# untitled2.net
KiCad netlist of a schematic drawn in EAGLE
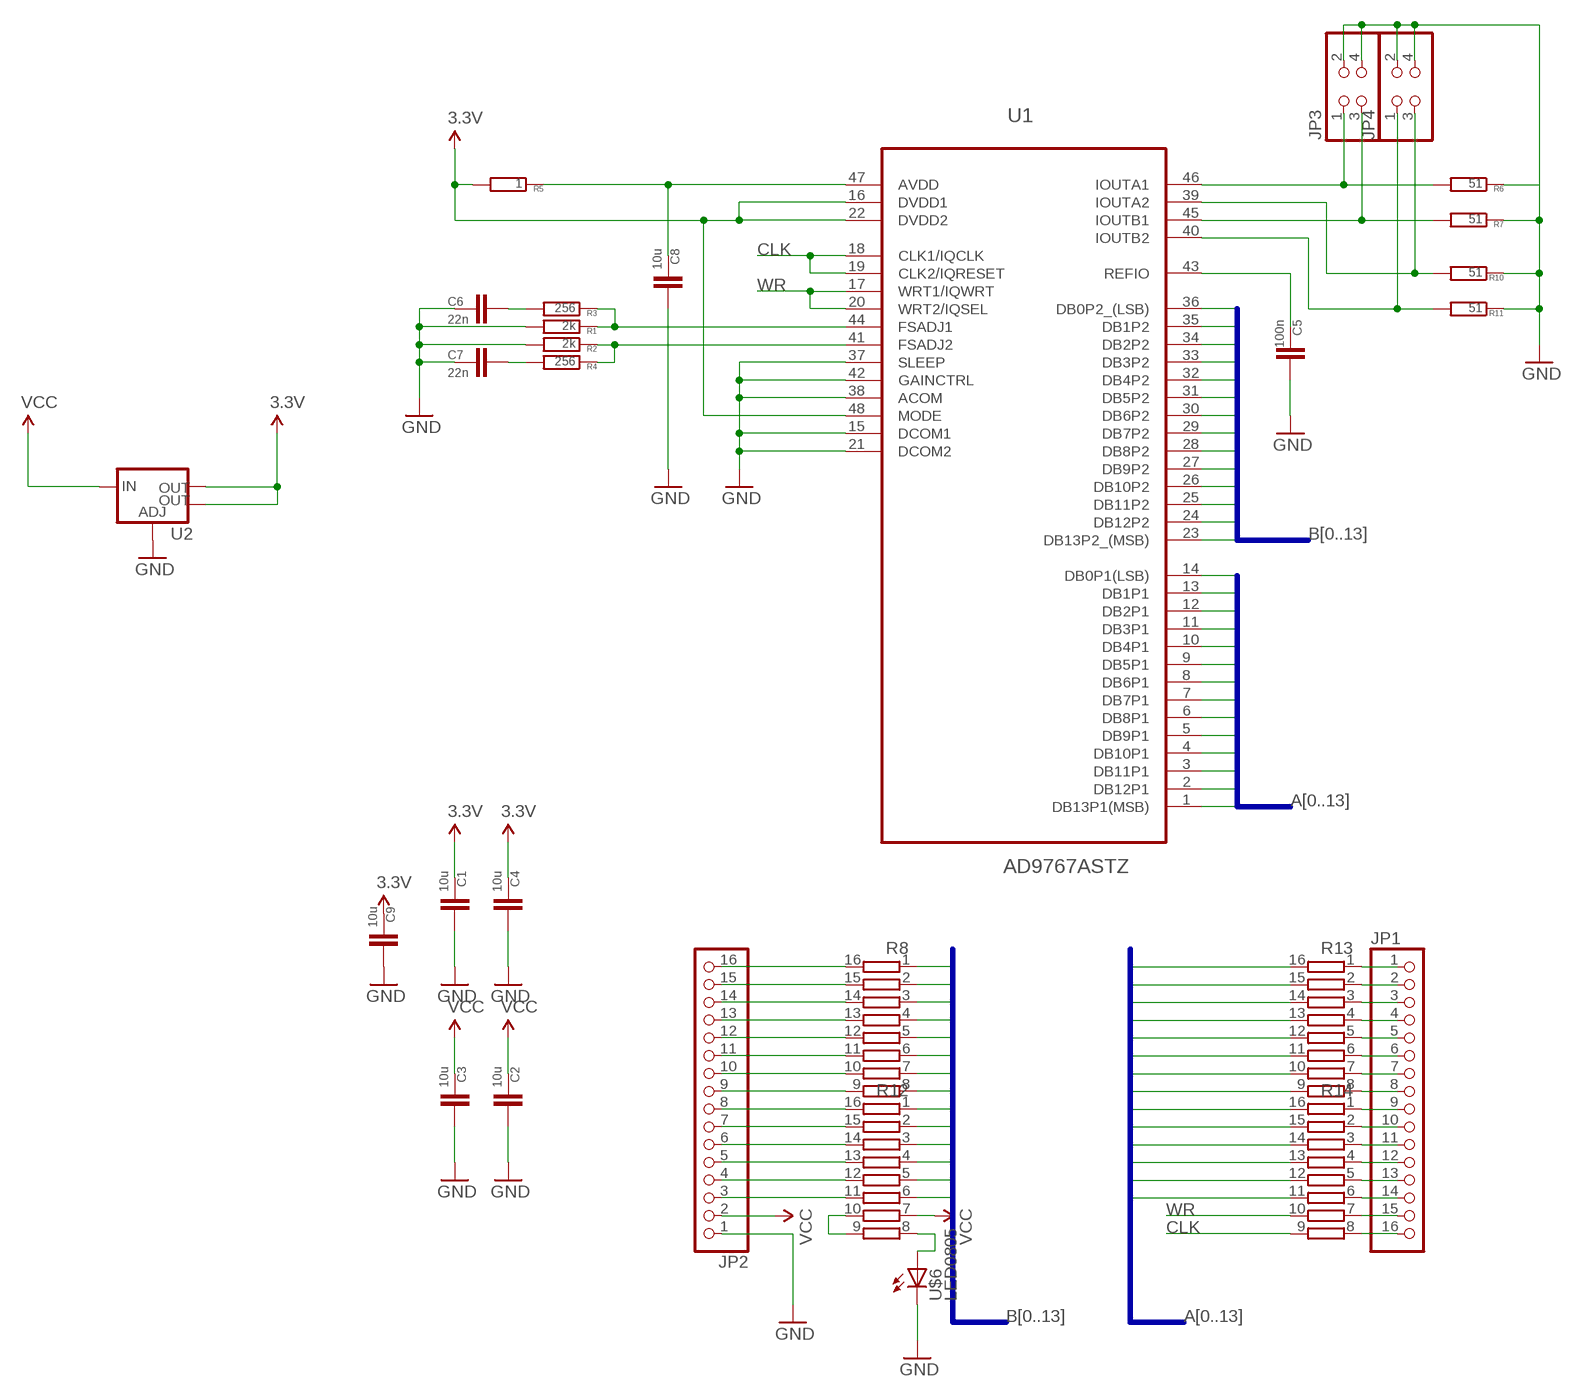
[diagram p0: schematic, sheet 1]

(export (version "E")
  (design (tool "Eeschema 10.0.6"))
  (components
    (comp (ref "C1")
      (value "10u")
      (footprint "eagle-import:C0805")
      (libsource (lib "eagle-import") (part "CC0805"))
    )
    (comp (ref "C2")
      (value "10u")
      (footprint "eagle-import:C0805")
      (libsource (lib "eagle-import") (part "CC0805"))
    )
    (comp (ref "C3")
      (value "10u")
      (footprint "eagle-import:C0805")
      (libsource (lib "eagle-import") (part "CC0805"))
    )
    (comp (ref "C4")
      (value "10u")
      (footprint "eagle-import:C0805")
      (libsource (lib "eagle-import") (part "CC0805"))
    )
    (comp (ref "C5")
      (value "100n")
      (footprint "eagle-import:C0805")
      (libsource (lib "eagle-import") (part "CC0805"))
    )
    (comp (ref "C6")
      (value "22n")
      (footprint "eagle-import:C0805")
      (libsource (lib "eagle-import") (part "CC0805"))
    )
    (comp (ref "C7")
      (value "22n")
      (footprint "eagle-import:C0805")
      (libsource (lib "eagle-import") (part "CC0805"))
    )
    (comp (ref "C8")
      (value "10u")
      (footprint "eagle-import:C0805")
      (libsource (lib "eagle-import") (part "CC0805"))
    )
    (comp (ref "C9")
      (value "10u")
      (footprint "eagle-import:C0805")
      (libsource (lib "eagle-import") (part "CC0805"))
    )
    (comp (ref "JP1")
      (value "PINHD-1X16_2.54")
      (footprint "eagle-import:1X16")
      (libsource (lib "eagle-import") (part "PINHD-1X16_2.54"))
    )
    (comp (ref "JP2")
      (value "PINHD-1X16_2.54")
      (footprint "eagle-import:1X16")
      (libsource (lib "eagle-import") (part "PINHD-1X16_2.54"))
    )
    (comp (ref "JP3")
      (value "PINHD-2X02_2.54-SMD")
      (footprint "eagle-import:2X02SMD")
      (libsource (lib "eagle-import") (part "PINHD-2X02_2.54-SMD"))
    )
    (comp (ref "JP4")
      (value "PINHD-2X02_2.54-SMD")
      (footprint "eagle-import:2X02SMD")
      (libsource (lib "eagle-import") (part "PINHD-2X02_2.54-SMD"))
    )
    (comp (ref "R1")
      (value "2k")
      (footprint "eagle-import:R0805")
      (libsource (lib "eagle-import") (part "R0805"))
    )
    (comp (ref "R2")
      (value "2k")
      (footprint "eagle-import:R0805")
      (libsource (lib "eagle-import") (part "R0805"))
    )
    (comp (ref "R3")
      (value "256")
      (footprint "eagle-import:R0805")
      (libsource (lib "eagle-import") (part "R0805"))
    )
    (comp (ref "R4")
      (value "256")
      (footprint "eagle-import:R0805")
      (libsource (lib "eagle-import") (part "R0805"))
    )
    (comp (ref "R5")
      (value "1")
      (footprint "eagle-import:0603")
      (libsource (lib "eagle-import") (part "R0603"))
    )
    (comp (ref "R6")
      (value "51")
      (footprint "eagle-import:R0805")
      (libsource (lib "eagle-import") (part "R0805"))
    )
    (comp (ref "R7")
      (value "51")
      (footprint "eagle-import:R0805")
      (libsource (lib "eagle-import") (part "R0805"))
    )
    (comp (ref "R8")
      (value "4816P-T01")
      (footprint "eagle-import:4816P")
      (fields (field (name "MF") "BOURNS, INC.") (field (name "MPN") "4816P-T01-684LF"))
      (libsource (lib "eagle-import") (part "4816P-T01"))
    )
    (comp (ref "R10")
      (value "51")
      (footprint "eagle-import:R0805")
      (libsource (lib "eagle-import") (part "R0805"))
    )
    (comp (ref "R11")
      (value "51")
      (footprint "eagle-import:R0805")
      (libsource (lib "eagle-import") (part "R0805"))
    )
    (comp (ref "R12")
      (value "4816P-T01")
      (footprint "eagle-import:4816P")
      (fields (field (name "MF") "BOURNS, INC.") (field (name "MPN") "4816P-T01-684LF"))
      (libsource (lib "eagle-import") (part "4816P-T01"))
    )
    (comp (ref "R13")
      (value "4816P-T01")
      (footprint "eagle-import:4816P")
      (fields (field (name "MF") "BOURNS, INC.") (field (name "MPN") "4816P-T01-684LF"))
      (libsource (lib "eagle-import") (part "4816P-T01"))
    )
    (comp (ref "R14")
      (value "4816P-T01")
      (footprint "eagle-import:4816P")
      (fields (field (name "MF") "BOURNS, INC.") (field (name "MPN") "4816P-T01-684LF"))
      (libsource (lib "eagle-import") (part "4816P-T01"))
    )
    (comp (ref "U$6")
      (value "LED0805")
      (footprint "eagle-import:0805-LED")
      (libsource (lib "eagle-import") (part "LED0805"))
    )
    (comp (ref "U1")
      (value "AD9767ASTZ")
      (footprint "eagle-import:QFP50P900X900X160-48N")
      (libsource (lib "eagle-import") (part "AD9767ASTZ"))
    )
    (comp (ref "U2")
      (value "V_REG_LM1117SOT223")
      (footprint "eagle-import:SOT223")
      (libsource (lib "eagle-import") (part "V_REG_LM1117SOT223"))
    )
  )
  (nets
    (net (code "1") (name "/A0") (class "Default")
      (node (ref "R14") (pin "11") (pinfunction "11_11") (pintype "passive"))
      (node (ref "U1") (pin "14") (pinfunction "DB0P1(LSB)_14") (pintype "bidirectional"))
    )
    (net (code "2") (name "/A1") (class "Default")
      (node (ref "R14") (pin "12") (pinfunction "12_12") (pintype "passive"))
      (node (ref "U1") (pin "13") (pinfunction "DB1P1_13") (pintype "bidirectional"))
    )
    (net (code "3") (name "/A2") (class "Default")
      (node (ref "R14") (pin "13") (pinfunction "13_13") (pintype "passive"))
      (node (ref "U1") (pin "12") (pinfunction "DB2P1_12") (pintype "bidirectional"))
    )
    (net (code "4") (name "/A3") (class "Default")
      (node (ref "R14") (pin "14") (pinfunction "14_14") (pintype "passive"))
      (node (ref "U1") (pin "11") (pinfunction "DB3P1_11") (pintype "bidirectional"))
    )
    (net (code "5") (name "/A4") (class "Default")
      (node (ref "R14") (pin "15") (pinfunction "15_15") (pintype "passive"))
      (node (ref "U1") (pin "10") (pinfunction "DB4P1_10") (pintype "bidirectional"))
    )
    (net (code "6") (name "/A5") (class "Default")
      (node (ref "R14") (pin "16") (pinfunction "16_16") (pintype "passive"))
      (node (ref "U1") (pin "9") (pinfunction "DB5P1_9") (pintype "bidirectional"))
    )
    (net (code "7") (name "/A6") (class "Default")
      (node (ref "R13") (pin "9") (pinfunction "9_9") (pintype "passive"))
      (node (ref "U1") (pin "8") (pinfunction "DB6P1_8") (pintype "bidirectional"))
    )
    (net (code "8") (name "/A7") (class "Default")
      (node (ref "R13") (pin "10") (pinfunction "10_10") (pintype "passive"))
      (node (ref "U1") (pin "7") (pinfunction "DB7P1_7") (pintype "bidirectional"))
    )
    (net (code "9") (name "/A8") (class "Default")
      (node (ref "R13") (pin "11") (pinfunction "11_11") (pintype "passive"))
      (node (ref "U1") (pin "6") (pinfunction "DB8P1_6") (pintype "bidirectional"))
    )
    (net (code "10") (name "/A9") (class "Default")
      (node (ref "R13") (pin "12") (pinfunction "12_12") (pintype "passive"))
      (node (ref "U1") (pin "5") (pinfunction "DB9P1_5") (pintype "bidirectional"))
    )
    (net (code "11") (name "/A10") (class "Default")
      (node (ref "R13") (pin "13") (pinfunction "13_13") (pintype "passive"))
      (node (ref "U1") (pin "4") (pinfunction "DB10P1_4") (pintype "bidirectional"))
    )
    (net (code "12") (name "/A11") (class "Default")
      (node (ref "R13") (pin "14") (pinfunction "14_14") (pintype "passive"))
      (node (ref "U1") (pin "3") (pinfunction "DB11P1_3") (pintype "bidirectional"))
    )
    (net (code "13") (name "/A12") (class "Default")
      (node (ref "R13") (pin "15") (pinfunction "15_15") (pintype "passive"))
      (node (ref "U1") (pin "2") (pinfunction "DB12P1_2") (pintype "bidirectional"))
    )
    (net (code "14") (name "/A13") (class "Default")
      (node (ref "R13") (pin "16") (pinfunction "16_16") (pintype "passive"))
      (node (ref "U1") (pin "1") (pinfunction "DB13P1(MSB)_1") (pintype "bidirectional"))
    )
    (net (code "16") (name "/B0") (class "Default")
      (node (ref "R8") (pin "1") (pinfunction "1_1") (pintype "passive"))
      (node (ref "U1") (pin "36") (pinfunction "DB0P2_(LSB)_36") (pintype "bidirectional"))
    )
    (net (code "17") (name "/B1") (class "Default")
      (node (ref "R8") (pin "2") (pinfunction "2_2") (pintype "passive"))
      (node (ref "U1") (pin "35") (pinfunction "DB1P2_35") (pintype "bidirectional"))
    )
    (net (code "18") (name "/B2") (class "Default")
      (node (ref "R8") (pin "3") (pinfunction "3_3") (pintype "passive"))
      (node (ref "U1") (pin "34") (pinfunction "DB2P2_34") (pintype "bidirectional"))
    )
    (net (code "19") (name "/B3") (class "Default")
      (node (ref "R8") (pin "4") (pinfunction "4_4") (pintype "passive"))
      (node (ref "U1") (pin "33") (pinfunction "DB3P2_33") (pintype "bidirectional"))
    )
    (net (code "20") (name "/B4") (class "Default")
      (node (ref "R8") (pin "5") (pinfunction "5_5") (pintype "passive"))
      (node (ref "U1") (pin "32") (pinfunction "DB4P2_32") (pintype "bidirectional"))
    )
    (net (code "21") (name "/B5") (class "Default")
      (node (ref "R8") (pin "6") (pinfunction "6_6") (pintype "passive"))
      (node (ref "U1") (pin "31") (pinfunction "DB5P2_31") (pintype "bidirectional"))
    )
    (net (code "22") (name "/B6") (class "Default")
      (node (ref "R8") (pin "7") (pinfunction "7_7") (pintype "passive"))
      (node (ref "U1") (pin "30") (pinfunction "DB6P2_30") (pintype "bidirectional"))
    )
    (net (code "23") (name "/B7") (class "Default")
      (node (ref "R8") (pin "8") (pinfunction "8_8") (pintype "passive"))
      (node (ref "U1") (pin "29") (pinfunction "DB7P2_29") (pintype "bidirectional"))
    )
    (net (code "24") (name "/B8") (class "Default")
      (node (ref "R12") (pin "1") (pinfunction "1_1") (pintype "passive"))
      (node (ref "U1") (pin "28") (pinfunction "DB8P2_28") (pintype "bidirectional"))
    )
    (net (code "25") (name "/B9") (class "Default")
      (node (ref "R12") (pin "2") (pinfunction "2_2") (pintype "passive"))
      (node (ref "U1") (pin "27") (pinfunction "DB9P2_27") (pintype "bidirectional"))
    )
    (net (code "26") (name "/B10") (class "Default")
      (node (ref "R12") (pin "3") (pinfunction "3_3") (pintype "passive"))
      (node (ref "U1") (pin "26") (pinfunction "DB10P2_26") (pintype "bidirectional"))
    )
    (net (code "27") (name "/B11") (class "Default")
      (node (ref "R12") (pin "4") (pinfunction "4_4") (pintype "passive"))
      (node (ref "U1") (pin "25") (pinfunction "DB11P2_25") (pintype "bidirectional"))
    )
    (net (code "28") (name "/B12") (class "Default")
      (node (ref "R12") (pin "5") (pinfunction "5_5") (pintype "passive"))
      (node (ref "U1") (pin "24") (pinfunction "DB12P2_24") (pintype "bidirectional"))
    )
    (net (code "29") (name "/B13") (class "Default")
      (node (ref "R12") (pin "6") (pinfunction "6_6") (pintype "passive"))
      (node (ref "U1") (pin "23") (pinfunction "DB13P2_(MSB)_23") (pintype "bidirectional"))
    )
    (net (code "31") (name "/CLK") (class "Default")
      (node (ref "R14") (pin "9") (pinfunction "9_9") (pintype "passive"))
      (node (ref "U1") (pin "18") (pinfunction "CLK1/IQCLK_18") (pintype "input"))
      (node (ref "U1") (pin "19") (pinfunction "CLK2/IQRESET_19") (pintype "input"))
    )
    (net (code "32") (name "/WR") (class "Default")
      (node (ref "R14") (pin "10") (pinfunction "10_10") (pintype "passive"))
      (node (ref "U1") (pin "17") (pinfunction "WRT1/IQWRT_17") (pintype "input"))
      (node (ref "U1") (pin "20") (pinfunction "WRT2/IQSEL_20") (pintype "input"))
    )
    (net (code "33") (name "3.3V") (class "Default")
      (node (ref "C1") (pin "2") (pinfunction "2_2") (pintype "passive"))
      (node (ref "C4") (pin "2") (pinfunction "2_2") (pintype "passive"))
      (node (ref "C9") (pin "2") (pinfunction "2_2") (pintype "passive"))
      (node (ref "R5") (pin "2") (pinfunction "2_2") (pintype "passive"))
      (node (ref "U1") (pin "16") (pinfunction "DVDD1_16") (pintype "power_in"))
      (node (ref "U1") (pin "22") (pinfunction "DVDD2_22") (pintype "power_in"))
      (node (ref "U1") (pin "48") (pinfunction "MODE_48") (pintype "passive"))
      (node (ref "U2") (pin "2") (pinfunction "OUT_2") (pintype "output"))
      (node (ref "U2") (pin "4") (pinfunction "OUT_4") (pintype "output"))
    )
    (net (code "34") (name "GND") (class "Default")
      (node (ref "C1") (pin "1") (pinfunction "1_1") (pintype "passive"))
      (node (ref "C2") (pin "1") (pinfunction "1_1") (pintype "passive"))
      (node (ref "C3") (pin "1") (pinfunction "1_1") (pintype "passive"))
      (node (ref "C4") (pin "1") (pinfunction "1_1") (pintype "passive"))
      (node (ref "C5") (pin "1") (pinfunction "1_1") (pintype "passive"))
      (node (ref "C6") (pin "2") (pinfunction "2_2") (pintype "passive"))
      (node (ref "C7") (pin "2") (pinfunction "2_2") (pintype "passive"))
      (node (ref "C8") (pin "1") (pinfunction "1_1") (pintype "passive"))
      (node (ref "C9") (pin "1") (pinfunction "1_1") (pintype "passive"))
      (node (ref "JP2") (pin "1") (pinfunction "1_1") (pintype "passive"))
      (node (ref "JP3") (pin "2") (pinfunction "2_2") (pintype "passive"))
      (node (ref "JP3") (pin "4") (pinfunction "4_4") (pintype "passive"))
      (node (ref "JP4") (pin "2") (pinfunction "2_2") (pintype "passive"))
      (node (ref "JP4") (pin "4") (pinfunction "4_4") (pintype "passive"))
      (node (ref "R1") (pin "2") (pinfunction "2_2") (pintype "passive"))
      (node (ref "R10") (pin "1") (pinfunction "1_1") (pintype "passive"))
      (node (ref "R11") (pin "1") (pinfunction "1_1") (pintype "passive"))
      (node (ref "R2") (pin "2") (pinfunction "2_2") (pintype "passive"))
      (node (ref "R6") (pin "1") (pinfunction "1_1") (pintype "passive"))
      (node (ref "R7") (pin "1") (pinfunction "1_1") (pintype "passive"))
      (node (ref "U$6") (pin "C") (pinfunction "C_C") (pintype "passive"))
      (node (ref "U1") (pin "15") (pinfunction "DCOM1_15") (pintype "passive"))
      (node (ref "U1") (pin "21") (pinfunction "DCOM2_21") (pintype "passive"))
      (node (ref "U1") (pin "37") (pinfunction "SLEEP_37") (pintype "passive"))
      (node (ref "U1") (pin "38") (pinfunction "ACOM_38") (pintype "passive"))
      (node (ref "U1") (pin "42") (pinfunction "GAINCTRL_42") (pintype "passive"))
      (node (ref "U2") (pin "1") (pinfunction "ADJ_1") (pintype "input"))
    )
    (net (code "35") (name "Net-(C6-Pad1)") (class "Default")
      (node (ref "C6") (pin "1") (pinfunction "1_1") (pintype "passive"))
      (node (ref "R3") (pin "2") (pinfunction "2_2") (pintype "passive"))
    )
    (net (code "36") (name "Net-(C7-Pad1)") (class "Default")
      (node (ref "C7") (pin "1") (pinfunction "1_1") (pintype "passive"))
      (node (ref "R4") (pin "2") (pinfunction "2_2") (pintype "passive"))
    )
    (net (code "37") (name "Net-(JP1-Pad1)") (class "Default")
      (node (ref "JP1") (pin "1") (pinfunction "1_1") (pintype "passive"))
      (node (ref "R13") (pin "1") (pinfunction "1_1") (pintype "passive"))
    )
    (net (code "38") (name "Net-(JP1-Pad2)") (class "Default")
      (node (ref "JP1") (pin "2") (pinfunction "2_2") (pintype "passive"))
      (node (ref "R13") (pin "2") (pinfunction "2_2") (pintype "passive"))
    )
    (net (code "39") (name "Net-(JP1-Pad3)") (class "Default")
      (node (ref "JP1") (pin "3") (pinfunction "3_3") (pintype "passive"))
      (node (ref "R13") (pin "3") (pinfunction "3_3") (pintype "passive"))
    )
    (net (code "40") (name "Net-(JP1-Pad4)") (class "Default")
      (node (ref "JP1") (pin "4") (pinfunction "4_4") (pintype "passive"))
      (node (ref "R13") (pin "4") (pinfunction "4_4") (pintype "passive"))
    )
    (net (code "41") (name "Net-(JP1-Pad5)") (class "Default")
      (node (ref "JP1") (pin "5") (pinfunction "5_5") (pintype "passive"))
      (node (ref "R13") (pin "5") (pinfunction "5_5") (pintype "passive"))
    )
    (net (code "42") (name "Net-(JP1-Pad6)") (class "Default")
      (node (ref "JP1") (pin "6") (pinfunction "6_6") (pintype "passive"))
      (node (ref "R13") (pin "6") (pinfunction "6_6") (pintype "passive"))
    )
    (net (code "43") (name "Net-(JP1-Pad7)") (class "Default")
      (node (ref "JP1") (pin "7") (pinfunction "7_7") (pintype "passive"))
      (node (ref "R13") (pin "7") (pinfunction "7_7") (pintype "passive"))
    )
    (net (code "44") (name "Net-(JP1-Pad8)") (class "Default")
      (node (ref "JP1") (pin "8") (pinfunction "8_8") (pintype "passive"))
      (node (ref "R13") (pin "8") (pinfunction "8_8") (pintype "passive"))
    )
    (net (code "45") (name "Net-(JP1-Pad9)") (class "Default")
      (node (ref "JP1") (pin "9") (pinfunction "9_9") (pintype "passive"))
      (node (ref "R14") (pin "1") (pinfunction "1_1") (pintype "passive"))
    )
    (net (code "46") (name "Net-(JP1-Pad10)") (class "Default")
      (node (ref "JP1") (pin "10") (pinfunction "10_10") (pintype "passive"))
      (node (ref "R14") (pin "2") (pinfunction "2_2") (pintype "passive"))
    )
    (net (code "47") (name "Net-(JP1-Pad11)") (class "Default")
      (node (ref "JP1") (pin "11") (pinfunction "11_11") (pintype "passive"))
      (node (ref "R14") (pin "3") (pinfunction "3_3") (pintype "passive"))
    )
    (net (code "48") (name "Net-(JP1-Pad12)") (class "Default")
      (node (ref "JP1") (pin "12") (pinfunction "12_12") (pintype "passive"))
      (node (ref "R14") (pin "4") (pinfunction "4_4") (pintype "passive"))
    )
    (net (code "49") (name "Net-(JP1-Pad13)") (class "Default")
      (node (ref "JP1") (pin "13") (pinfunction "13_13") (pintype "passive"))
      (node (ref "R14") (pin "5") (pinfunction "5_5") (pintype "passive"))
    )
    (net (code "50") (name "Net-(JP1-Pad14)") (class "Default")
      (node (ref "JP1") (pin "14") (pinfunction "14_14") (pintype "passive"))
      (node (ref "R14") (pin "6") (pinfunction "6_6") (pintype "passive"))
    )
    (net (code "51") (name "Net-(JP1-Pad15)") (class "Default")
      (node (ref "JP1") (pin "15") (pinfunction "15_15") (pintype "passive"))
      (node (ref "R14") (pin "7") (pinfunction "7_7") (pintype "passive"))
    )
    (net (code "52") (name "Net-(JP1-Pad16)") (class "Default")
      (node (ref "JP1") (pin "16") (pinfunction "16_16") (pintype "passive"))
      (node (ref "R14") (pin "8") (pinfunction "8_8") (pintype "passive"))
    )
    (net (code "53") (name "Net-(JP2-Pad3)") (class "Default")
      (node (ref "JP2") (pin "3") (pinfunction "3_3") (pintype "passive"))
      (node (ref "R12") (pin "11") (pinfunction "11_11") (pintype "passive"))
    )
    (net (code "54") (name "Net-(JP2-Pad4)") (class "Default")
      (node (ref "JP2") (pin "4") (pinfunction "4_4") (pintype "passive"))
      (node (ref "R12") (pin "12") (pinfunction "12_12") (pintype "passive"))
    )
    (net (code "55") (name "Net-(JP2-Pad5)") (class "Default")
      (node (ref "JP2") (pin "5") (pinfunction "5_5") (pintype "passive"))
      (node (ref "R12") (pin "13") (pinfunction "13_13") (pintype "passive"))
    )
    (net (code "56") (name "Net-(JP2-Pad6)") (class "Default")
      (node (ref "JP2") (pin "6") (pinfunction "6_6") (pintype "passive"))
      (node (ref "R12") (pin "14") (pinfunction "14_14") (pintype "passive"))
    )
    (net (code "57") (name "Net-(JP2-Pad7)") (class "Default")
      (node (ref "JP2") (pin "7") (pinfunction "7_7") (pintype "passive"))
      (node (ref "R12") (pin "15") (pinfunction "15_15") (pintype "passive"))
    )
    (net (code "58") (name "Net-(JP2-Pad8)") (class "Default")
      (node (ref "JP2") (pin "8") (pinfunction "8_8") (pintype "passive"))
      (node (ref "R12") (pin "16") (pinfunction "16_16") (pintype "passive"))
    )
    (net (code "59") (name "Net-(JP2-Pad9)") (class "Default")
      (node (ref "JP2") (pin "9") (pinfunction "9_9") (pintype "passive"))
      (node (ref "R8") (pin "9") (pinfunction "9_9") (pintype "passive"))
    )
    (net (code "60") (name "Net-(JP2-Pad10)") (class "Default")
      (node (ref "JP2") (pin "10") (pinfunction "10_10") (pintype "passive"))
      (node (ref "R8") (pin "10") (pinfunction "10_10") (pintype "passive"))
    )
    (net (code "61") (name "Net-(JP2-Pad11)") (class "Default")
      (node (ref "JP2") (pin "11") (pinfunction "11_11") (pintype "passive"))
      (node (ref "R8") (pin "11") (pinfunction "11_11") (pintype "passive"))
    )
    (net (code "62") (name "Net-(JP2-Pad12)") (class "Default")
      (node (ref "JP2") (pin "12") (pinfunction "12_12") (pintype "passive"))
      (node (ref "R8") (pin "12") (pinfunction "12_12") (pintype "passive"))
    )
    (net (code "63") (name "Net-(JP2-Pad13)") (class "Default")
      (node (ref "JP2") (pin "13") (pinfunction "13_13") (pintype "passive"))
      (node (ref "R8") (pin "13") (pinfunction "13_13") (pintype "passive"))
    )
    (net (code "64") (name "Net-(JP2-Pad14)") (class "Default")
      (node (ref "JP2") (pin "14") (pinfunction "14_14") (pintype "passive"))
      (node (ref "R8") (pin "14") (pinfunction "14_14") (pintype "passive"))
    )
    (net (code "65") (name "Net-(JP2-Pad15)") (class "Default")
      (node (ref "JP2") (pin "15") (pinfunction "15_15") (pintype "passive"))
      (node (ref "R8") (pin "15") (pinfunction "15_15") (pintype "passive"))
    )
    (net (code "66") (name "Net-(JP2-Pad16)") (class "Default")
      (node (ref "JP2") (pin "16") (pinfunction "16_16") (pintype "passive"))
      (node (ref "R8") (pin "16") (pinfunction "16_16") (pintype "passive"))
    )
    (net (code "67") (name "Net-(R12-Pad8)") (class "Default")
      (node (ref "R12") (pin "8") (pinfunction "8_8") (pintype "passive"))
      (node (ref "U$6") (pin "A") (pinfunction "A_A") (pintype "passive"))
    )
    (net (code "68") (name "Net-(R12-Pad10)") (class "Default")
      (node (ref "R12") (pin "10") (pinfunction "10_10") (pintype "passive"))
      (node (ref "R12") (pin "9") (pinfunction "9_9") (pintype "passive"))
    )
    (net (code "69") (name "Net-(U1-AVDD)") (class "Default")
      (node (ref "C8") (pin "2") (pinfunction "2_2") (pintype "passive"))
      (node (ref "R5") (pin "1") (pinfunction "1_1") (pintype "passive"))
      (node (ref "U1") (pin "47") (pinfunction "AVDD_47") (pintype "power_in"))
    )
    (net (code "70") (name "Net-(U1-FSADJ1)") (class "Default")
      (node (ref "R1") (pin "1") (pinfunction "1_1") (pintype "passive"))
      (node (ref "R3") (pin "1") (pinfunction "1_1") (pintype "passive"))
      (node (ref "U1") (pin "44") (pinfunction "FSADJ1_44") (pintype "passive"))
    )
    (net (code "71") (name "Net-(U1-FSADJ2)") (class "Default")
      (node (ref "R2") (pin "1") (pinfunction "1_1") (pintype "passive"))
      (node (ref "R4") (pin "1") (pinfunction "1_1") (pintype "passive"))
      (node (ref "U1") (pin "41") (pinfunction "FSADJ2_41") (pintype "passive"))
    )
    (net (code "72") (name "Net-(U1-IOUTA1)") (class "Default")
      (node (ref "JP3") (pin "1") (pinfunction "1_1") (pintype "passive"))
      (node (ref "R6") (pin "2") (pinfunction "2_2") (pintype "passive"))
      (node (ref "U1") (pin "46") (pinfunction "IOUTA1_46") (pintype "output"))
    )
    (net (code "73") (name "Net-(U1-IOUTA2)") (class "Default")
      (node (ref "JP4") (pin "3") (pinfunction "3_3") (pintype "passive"))
      (node (ref "R10") (pin "2") (pinfunction "2_2") (pintype "passive"))
      (node (ref "U1") (pin "39") (pinfunction "IOUTA2_39") (pintype "output"))
    )
    (net (code "74") (name "Net-(U1-IOUTB1)") (class "Default")
      (node (ref "JP3") (pin "3") (pinfunction "3_3") (pintype "passive"))
      (node (ref "R7") (pin "2") (pinfunction "2_2") (pintype "passive"))
      (node (ref "U1") (pin "45") (pinfunction "IOUTB1_45") (pintype "output"))
    )
    (net (code "75") (name "Net-(U1-IOUTB2)") (class "Default")
      (node (ref "JP4") (pin "1") (pinfunction "1_1") (pintype "passive"))
      (node (ref "R11") (pin "2") (pinfunction "2_2") (pintype "passive"))
      (node (ref "U1") (pin "40") (pinfunction "IOUTB2_40") (pintype "output"))
    )
    (net (code "76") (name "Net-(U1-REFIO)") (class "Default")
      (node (ref "C5") (pin "2") (pinfunction "2_2") (pintype "passive"))
      (node (ref "U1") (pin "43") (pinfunction "REFIO_43") (pintype "bidirectional"))
    )
    (net (code "77") (name "VCC") (class "Default")
      (node (ref "C2") (pin "2") (pinfunction "2_2") (pintype "passive"))
      (node (ref "C3") (pin "2") (pinfunction "2_2") (pintype "passive"))
      (node (ref "JP2") (pin "2") (pinfunction "2_2") (pintype "passive"))
      (node (ref "R12") (pin "7") (pinfunction "7_7") (pintype "passive"))
      (node (ref "U2") (pin "3") (pinfunction "IN_3") (pintype "input"))
    )
  )
)
